# eggShield.net
KiCad netlist of a schematic drawn in EAGLE
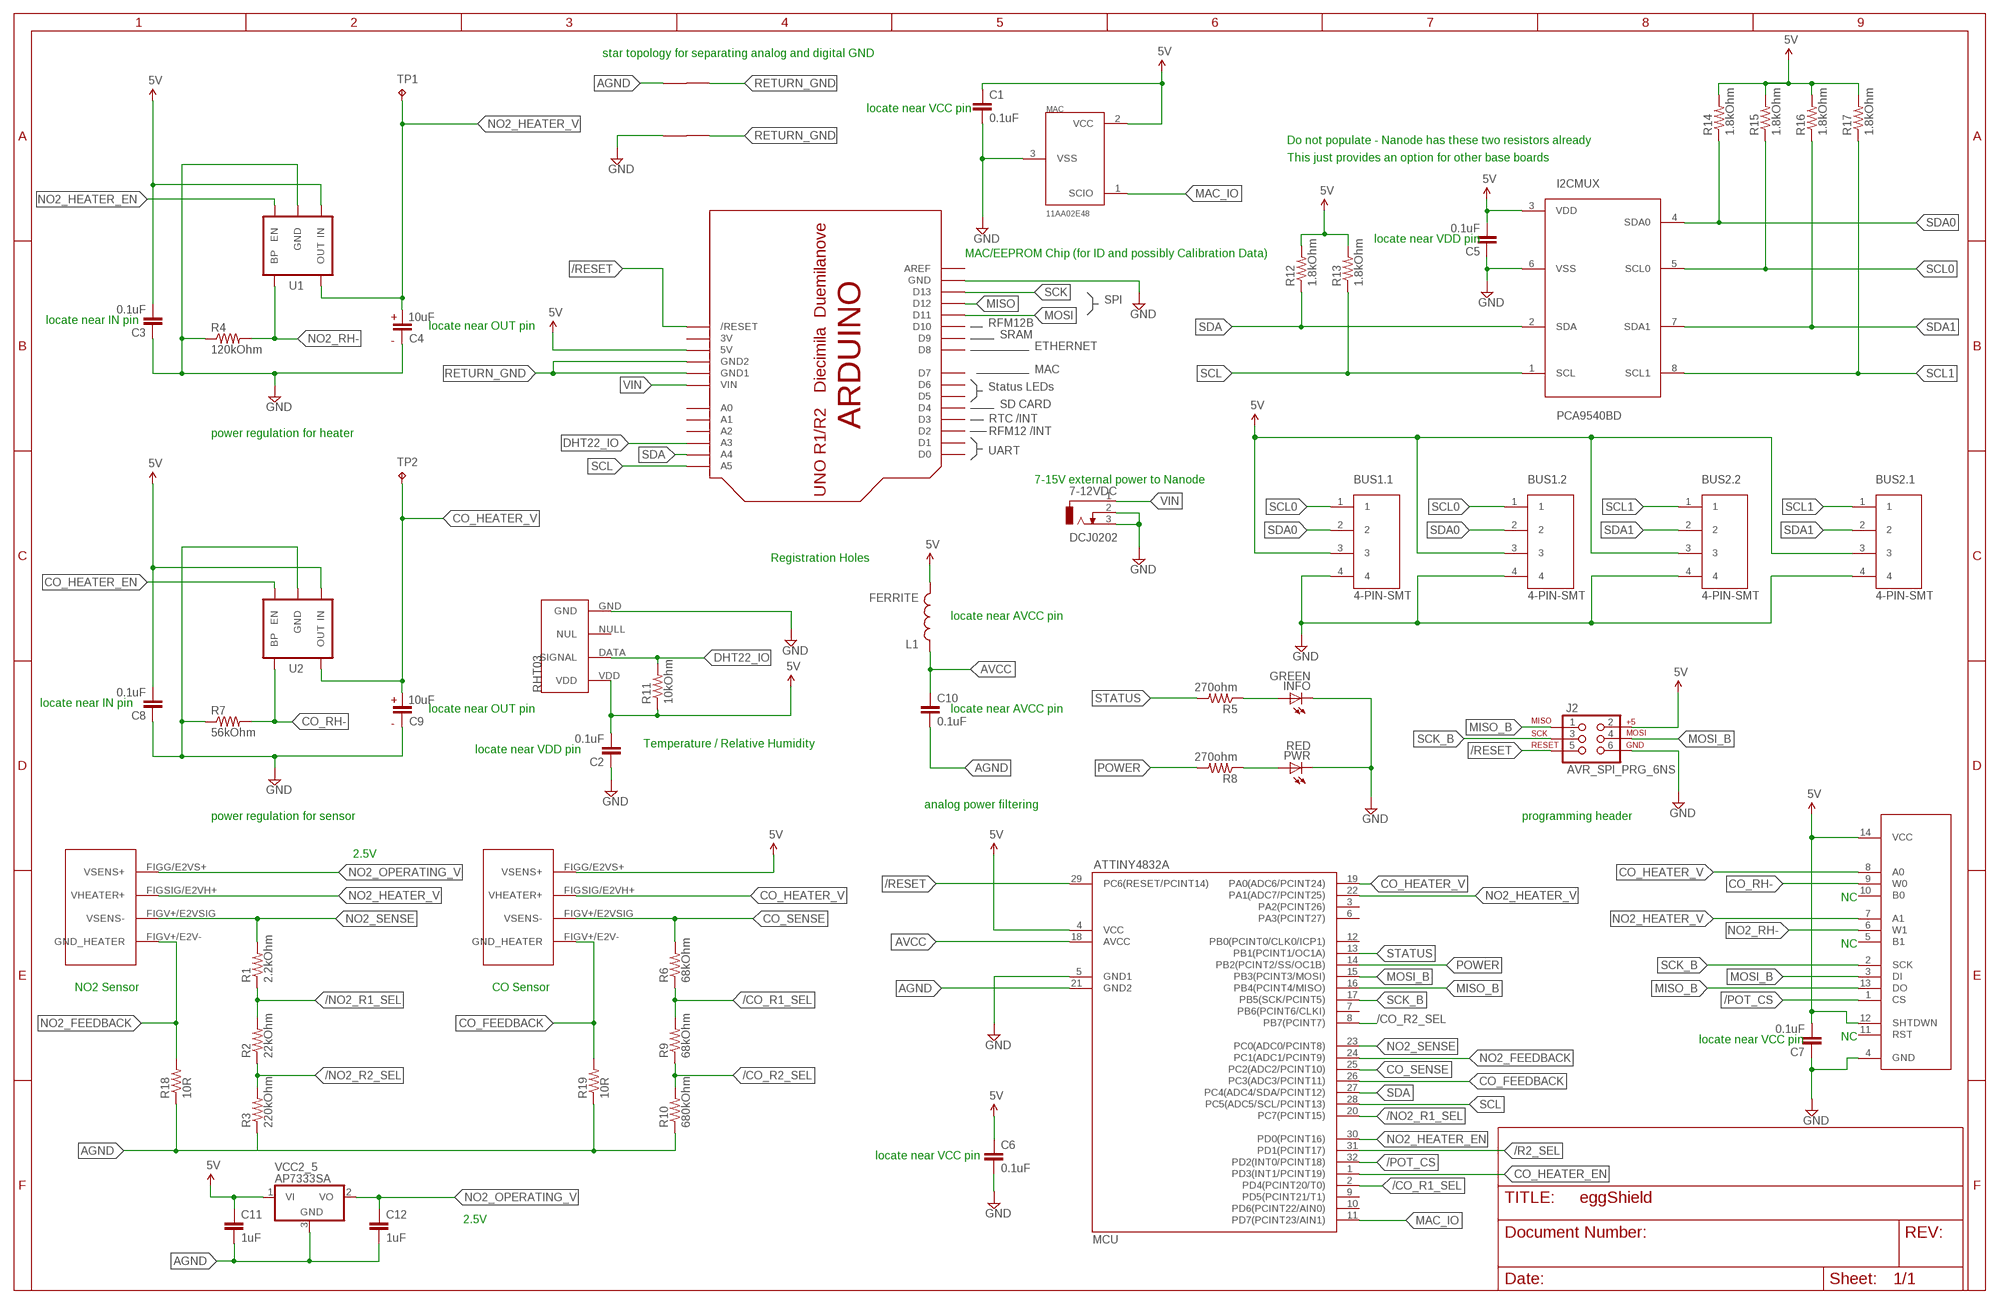
[diagram p0: schematic, sheet 1]

(export (version "E")
  (design (tool "Eeschema 10.0.6"))
  (components
    (comp (ref "7-12VDC")
      (value "DCJ0202")
      (footprint "eagle-import:DCJ0202")
      (libsource (lib "eagle-import") (part "DCJ0202"))
    )
    (comp (ref "BUS1.1")
      (value "4-PIN-SMT")
      (footprint "eagle-import:1775470-4")
      (libsource (lib "eagle-import") (part "4-PIN-SMT"))
    )
    (comp (ref "BUS1.2")
      (value "4-PIN-SMT")
      (footprint "eagle-import:1775470-4")
      (libsource (lib "eagle-import") (part "4-PIN-SMT"))
    )
    (comp (ref "BUS2.1")
      (value "4-PIN-SMT")
      (footprint "eagle-import:1775470-4")
      (libsource (lib "eagle-import") (part "4-PIN-SMT"))
    )
    (comp (ref "BUS2.2")
      (value "4-PIN-SMT")
      (footprint "eagle-import:1775470-4")
      (libsource (lib "eagle-import") (part "4-PIN-SMT"))
    )
    (comp (ref "C1")
      (value "0.1uF")
      (footprint "eagle-import:0805")
      (libsource (lib "eagle-import") (part "SparkFun-Passives_CAP0805"))
    )
    (comp (ref "C2")
      (value "0.1uF")
      (footprint "eagle-import:0805")
      (libsource (lib "eagle-import") (part "SparkFun-Passives_CAP0805"))
    )
    (comp (ref "C3")
      (value "0.1uF")
      (footprint "eagle-import:0805")
      (libsource (lib "eagle-import") (part "SparkFun-Passives_CAP0805"))
    )
    (comp (ref "C4")
      (value "10uF")
      (footprint "eagle-import:TYPE-B_ALUMINUM_CAN")
      (libsource (lib "eagle-import") (part "EEE-1EA100WR"))
    )
    (comp (ref "C5")
      (value "0.1uF")
      (footprint "eagle-import:0805")
      (libsource (lib "eagle-import") (part "SparkFun-Passives_CAP0805"))
    )
    (comp (ref "C6")
      (value "0.1uF")
      (footprint "eagle-import:0805")
      (libsource (lib "eagle-import") (part "SparkFun-Passives_CAP0805"))
    )
    (comp (ref "C7")
      (value "0.1uF")
      (footprint "eagle-import:0805")
      (libsource (lib "eagle-import") (part "SparkFun-Passives_CAP0805"))
    )
    (comp (ref "C8")
      (value "0.1uF")
      (footprint "eagle-import:0805")
      (libsource (lib "eagle-import") (part "SparkFun-Passives_CAP0805"))
    )
    (comp (ref "C9")
      (value "10uF")
      (footprint "eagle-import:TYPE-B_ALUMINUM_CAN")
      (libsource (lib "eagle-import") (part "EEE-1EA100WR"))
    )
    (comp (ref "C10")
      (value "0.1uF")
      (footprint "eagle-import:0805")
      (libsource (lib "eagle-import") (part "SparkFun-Passives_CAP0805"))
    )
    (comp (ref "C11")
      (value "1uF")
      (footprint "eagle-import:0805")
      (libsource (lib "eagle-import") (part "SparkFun-Passives_CAP0805"))
    )
    (comp (ref "C12")
      (value "1uF")
      (footprint "eagle-import:0805")
      (libsource (lib "eagle-import") (part "SparkFun-Passives_CAP0805"))
    )
    (comp (ref "CO")
      (value "E2V")
      (footprint "eagle-import:SR-4")
      (libsource (lib "eagle-import") (part "E2V"))
    )
    (comp (ref "DHT22")
      (value "RHT03")
      (footprint "eagle-import:1X04_LOCK")
      (libsource (lib "eagle-import") (part "RHT03"))
    )
    (comp (ref "I2CMUX")
      (value "PCA9540BD")
      (footprint "eagle-import:SO8")
      (libsource (lib "eagle-import") (part "PCA9540BD"))
    )
    (comp (ref "INFO")
      (value "GREEN")
      (footprint "eagle-import:CHIPLED_0805")
      (libsource (lib "eagle-import") (part "LEDCHIPLED_0805"))
    )
    (comp (ref "J2")
      (value "AVR_SPI_PRG_6NS")
      (footprint "eagle-import:2X3-NS")
      (libsource (lib "eagle-import") (part "AVR_SPI_PRG_6NS"))
    )
    (comp (ref "L1")
      (value "FERRITE")
      (footprint "eagle-import:0805")
      (libsource (lib "eagle-import") (part "INDUCTOR0805"))
    )
    (comp (ref "MAC")
      (value "11AA02E48")
      (footprint "eagle-import:SOT23")
      (libsource (lib "eagle-import") (part "11AA02E48"))
    )
    (comp (ref "MCU")
      (value "ATTINY4832A")
      (footprint "eagle-import:TQFP32-08")
      (libsource (lib "eagle-import") (part "ATTINY4832A"))
    )
    (comp (ref "N02")
      (value "E2V")
      (footprint "eagle-import:SR-4")
      (libsource (lib "eagle-import") (part "E2V"))
    )
    (comp (ref "PWR")
      (value "RED")
      (footprint "eagle-import:CHIPLED_0805")
      (libsource (lib "eagle-import") (part "LEDCHIPLED_0805"))
    )
    (comp (ref "R1")
      (value "2.2kOhm")
      (footprint "eagle-import:0805")
      (libsource (lib "eagle-import") (part "RESISTOR0805-RES"))
    )
    (comp (ref "R2")
      (value "22kOhm")
      (footprint "eagle-import:0805")
      (libsource (lib "eagle-import") (part "RESISTOR0805-RES"))
    )
    (comp (ref "R3")
      (value "220kOhm")
      (footprint "eagle-import:0805")
      (libsource (lib "eagle-import") (part "RESISTOR0805-RES"))
    )
    (comp (ref "R4")
      (value "120kOhm")
      (footprint "eagle-import:0805")
      (libsource (lib "eagle-import") (part "RESISTOR0805-RES"))
    )
    (comp (ref "R5")
      (value "270ohm")
      (footprint "eagle-import:0805")
      (libsource (lib "eagle-import") (part "RESISTOR0805-RES"))
    )
    (comp (ref "R6")
      (value "68kOhm")
      (footprint "eagle-import:0805")
      (libsource (lib "eagle-import") (part "RESISTOR0805-RES"))
    )
    (comp (ref "R7")
      (value "56kOhm")
      (footprint "eagle-import:0805")
      (libsource (lib "eagle-import") (part "RESISTOR0805-RES"))
    )
    (comp (ref "R8")
      (value "270ohm")
      (footprint "eagle-import:0805")
      (libsource (lib "eagle-import") (part "RESISTOR0805-RES"))
    )
    (comp (ref "R9")
      (value "68kOhm")
      (footprint "eagle-import:0805")
      (libsource (lib "eagle-import") (part "RESISTOR0805-RES"))
    )
    (comp (ref "R10")
      (value "680kOhm")
      (footprint "eagle-import:0805")
      (libsource (lib "eagle-import") (part "RESISTOR0805-RES"))
    )
    (comp (ref "R11")
      (value "10kOhm")
      (footprint "eagle-import:0805")
      (libsource (lib "eagle-import") (part "RESISTOR0805-RES"))
    )
    (comp (ref "R12")
      (value "1.8kOhm")
      (footprint "eagle-import:0805")
      (libsource (lib "eagle-import") (part "RESISTOR0805-RES"))
    )
    (comp (ref "R13")
      (value "1.8kOhm")
      (footprint "eagle-import:0805")
      (libsource (lib "eagle-import") (part "RESISTOR0805-RES"))
    )
    (comp (ref "R14")
      (value "1.8kOhm")
      (footprint "eagle-import:0805")
      (libsource (lib "eagle-import") (part "RESISTOR0805-RES"))
    )
    (comp (ref "R15")
      (value "1.8kOhm")
      (footprint "eagle-import:0805")
      (libsource (lib "eagle-import") (part "RESISTOR0805-RES"))
    )
    (comp (ref "R16")
      (value "1.8kOhm")
      (footprint "eagle-import:0805")
      (libsource (lib "eagle-import") (part "RESISTOR0805-RES"))
    )
    (comp (ref "R17")
      (value "1.8kOhm")
      (footprint "eagle-import:0805")
      (libsource (lib "eagle-import") (part "RESISTOR0805-RES"))
    )
    (comp (ref "R18")
      (value "10R")
      (footprint "eagle-import:0805")
      (libsource (lib "eagle-import") (part "RESISTOR0805-RES"))
    )
    (comp (ref "R19")
      (value "10R")
      (footprint "eagle-import:0805")
      (libsource (lib "eagle-import") (part "RESISTOR0805-RES"))
    )
    (comp (ref "TP1")
      (value "TPPAD1-13")
      (footprint "eagle-import:P1-13")
      (libsource (lib "eagle-import") (part "TPPAD1-13"))
    )
    (comp (ref "TP2")
      (value "TPPAD1-13")
      (footprint "eagle-import:P1-13")
      (libsource (lib "eagle-import") (part "TPPAD1-13"))
    )
    (comp (ref "U$7")
      (value "ARDUINO-NOHOLE")
      (footprint "eagle-import:ARDUINO-NOHOLE")
      (libsource (lib "eagle-import") (part "ARDUINO-NOHOLE"))
    )
    (comp (ref "U$13")
      (value "PLANE_COUPLER")
      (footprint "eagle-import:PLANE_COUPLER")
      (libsource (lib "eagle-import") (part "PLANE_COUPLER"))
    )
    (comp (ref "U$14")
      (value "PLANE_COUPLER")
      (footprint "eagle-import:PLANE_COUPLER")
      (libsource (lib "eagle-import") (part "PLANE_COUPLER"))
    )
    (comp (ref "U1")
      (value "V_REG_LDOSMD")
      (footprint "eagle-import:SOT23-5")
      (libsource (lib "eagle-import") (part "V_REG_LDOSMD"))
    )
    (comp (ref "U2")
      (value "V_REG_LDOSMD")
      (footprint "eagle-import:SOT23-5")
      (libsource (lib "eagle-import") (part "V_REG_LDOSMD"))
    )
    (comp (ref "U3")
      (value "MCP42XXX")
      (footprint "eagle-import:SO014")
      (libsource (lib "eagle-import") (part "MCP42XXX"))
    )
    (comp (ref "VCC2_5")
      (value "AP7333SA")
      (footprint "eagle-import:SOT-23-3")
      (libsource (lib "eagle-import") (part "AP7333SA"))
    )
  )
  (nets
    (net (code "1") (name "/3V") (class "Default")
      (node (ref "U$7") (pin "3V") (pinfunction "3V_3V") (pintype "power_in"))
    )
    (net (code "2") (name "5V") (class "Default")
      (node (ref "BUS1.1") (pin "3") (pinfunction "3_3") (pintype "bidirectional"))
      (node (ref "BUS1.2") (pin "3") (pinfunction "3_3") (pintype "bidirectional"))
      (node (ref "BUS2.1") (pin "3") (pinfunction "3_3") (pintype "bidirectional"))
      (node (ref "BUS2.2") (pin "3") (pinfunction "3_3") (pintype "bidirectional"))
      (node (ref "C1") (pin "1") (pinfunction "1_1") (pintype "passive"))
      (node (ref "C11") (pin "1") (pinfunction "1_1") (pintype "passive"))
      (node (ref "C2") (pin "2") (pinfunction "2_2") (pintype "passive"))
      (node (ref "C3") (pin "2") (pinfunction "2_2") (pintype "passive"))
      (node (ref "C5") (pin "2") (pinfunction "2_2") (pintype "passive"))
      (node (ref "C6") (pin "1") (pinfunction "1_1") (pintype "passive"))
      (node (ref "C7") (pin "2") (pinfunction "2_2") (pintype "passive"))
      (node (ref "C8") (pin "2") (pinfunction "2_2") (pintype "passive"))
      (node (ref "CO") (pin "FIGG/E2VS+") (pinfunction "VSENS+_FIGG/E2VS+") (pintype "bidirectional"))
      (node (ref "DHT22") (pin "VDD") (pinfunction "VDD_VDD") (pintype "bidirectional"))
      (node (ref "I2CMUX") (pin "3") (pinfunction "VDD_3") (pintype "power_in"))
      (node (ref "J2") (pin "2") (pinfunction "2_2") (pintype "passive"))
      (node (ref "L1") (pin "2") (pinfunction "2_2") (pintype "passive"))
      (node (ref "MAC") (pin "2") (pinfunction "VCC_2") (pintype "bidirectional"))
      (node (ref "MCU") (pin "4") (pinfunction "VCC_4") (pintype "power_in"))
      (node (ref "R11") (pin "1") (pinfunction "1_1") (pintype "passive"))
      (node (ref "R12") (pin "2") (pinfunction "2_2") (pintype "passive"))
      (node (ref "R13") (pin "2") (pinfunction "2_2") (pintype "passive"))
      (node (ref "R14") (pin "2") (pinfunction "2_2") (pintype "passive"))
      (node (ref "R15") (pin "2") (pinfunction "2_2") (pintype "passive"))
      (node (ref "R16") (pin "2") (pinfunction "2_2") (pintype "passive"))
      (node (ref "R17") (pin "2") (pinfunction "2_2") (pintype "passive"))
      (node (ref "U$7") (pin "5V") (pinfunction "5V_5V") (pintype "power_in"))
      (node (ref "U1") (pin "1") (pinfunction "IN_1") (pintype "input"))
      (node (ref "U2") (pin "1") (pinfunction "IN_1") (pintype "input"))
      (node (ref "U3") (pin "12") (pinfunction "SHTDWN_12") (pintype "bidirectional"))
      (node (ref "U3") (pin "14") (pinfunction "VCC_14") (pintype "bidirectional"))
      (node (ref "VCC2_5") (pin "1") (pinfunction "VI_1") (pintype "input"))
    )
    (net (code "3") (name "AGND") (class "Default")
      (node (ref "C10") (pin "2") (pinfunction "2_2") (pintype "passive"))
      (node (ref "C11") (pin "2") (pinfunction "2_2") (pintype "passive"))
      (node (ref "C12") (pin "2") (pinfunction "2_2") (pintype "passive"))
      (node (ref "MCU") (pin "21") (pinfunction "GND2_21") (pintype "power_in"))
      (node (ref "R10") (pin "1") (pinfunction "1_1") (pintype "passive"))
      (node (ref "R18") (pin "1") (pinfunction "1_1") (pintype "passive"))
      (node (ref "R19") (pin "1") (pinfunction "1_1") (pintype "passive"))
      (node (ref "R3") (pin "1") (pinfunction "1_1") (pintype "passive"))
      (node (ref "U$13") (pin "1") (pinfunction "P$1_1") (pintype "bidirectional"))
      (node (ref "VCC2_5") (pin "3") (pinfunction "GND_3") (pintype "input"))
    )
    (net (code "4") (name "AVCC") (class "Default")
      (node (ref "C10") (pin "1") (pinfunction "1_1") (pintype "passive"))
      (node (ref "L1") (pin "1") (pinfunction "1_1") (pintype "passive"))
      (node (ref "MCU") (pin "18") (pinfunction "AVCC_18") (pintype "power_in"))
    )
    (net (code "5") (name "CO_FEEDBACK") (class "Default")
      (node (ref "CO") (pin "FIGV+/E2V-") (pinfunction "GND_HEATER_FIGV+/E2V-") (pintype "bidirectional"))
      (node (ref "MCU") (pin "26") (pinfunction "PC3(ADC3/PCINT11)_26") (pintype "bidirectional"))
      (node (ref "R19") (pin "2") (pinfunction "2_2") (pintype "passive"))
    )
    (net (code "6") (name "CO_HEATER_EN") (class "Default")
      (node (ref "MCU") (pin "1") (pinfunction "PD3(INT1/PCINT19)_1") (pintype "bidirectional"))
      (node (ref "U2") (pin "3") (pinfunction "EN_3") (pintype "input"))
    )
    (net (code "7") (name "CO_HEATER_V") (class "Default")
      (node (ref "C9") (pin "P$1") (pinfunction "1_P$1") (pintype "passive"))
      (node (ref "CO") (pin "FIGSIG/E2VH+") (pinfunction "VHEATER+_FIGSIG/E2VH+") (pintype "bidirectional"))
      (node (ref "MCU") (pin "19") (pinfunction "PA0(ADC6/PCINT24)_19") (pintype "bidirectional"))
      (node (ref "TP2") (pin "TP") (pinfunction "TP_TP") (pintype "input"))
      (node (ref "U2") (pin "5") (pinfunction "OUT_5") (pintype "passive"))
      (node (ref "U3") (pin "8") (pinfunction "A0_8") (pintype "bidirectional"))
    )
    (net (code "8") (name "CO_RH-") (class "Default")
      (node (ref "R7") (pin "2") (pinfunction "2_2") (pintype "passive"))
      (node (ref "U2") (pin "4") (pinfunction "BP_4") (pintype "input"))
      (node (ref "U3") (pin "9") (pinfunction "W0_9") (pintype "bidirectional"))
    )
    (net (code "9") (name "CO_SENSE") (class "Default")
      (node (ref "CO") (pin "FIGV+/E2VSIG") (pinfunction "VSENS-_FIGV+/E2VSIG") (pintype "bidirectional"))
      (node (ref "MCU") (pin "25") (pinfunction "PC2(ADC2/PCINT10)_25") (pintype "bidirectional"))
      (node (ref "R6") (pin "2") (pinfunction "2_2") (pintype "passive"))
    )
    (net (code "10") (name "DHT22_IO") (class "Default")
      (node (ref "DHT22") (pin "DATA") (pinfunction "SIGNAL_DATA") (pintype "bidirectional"))
      (node (ref "R11") (pin "2") (pinfunction "2_2") (pintype "passive"))
      (node (ref "U$7") (pin "A3") (pinfunction "A3_A3") (pintype "bidirectional"))
    )
    (net (code "11") (name "GND") (class "Default")
      (node (ref "7-12VDC") (pin "2") (pinfunction "2_2") (pintype "passive"))
      (node (ref "7-12VDC") (pin "3") (pinfunction "3_3") (pintype "passive"))
      (node (ref "BUS1.1") (pin "4") (pinfunction "4_4") (pintype "bidirectional"))
      (node (ref "BUS1.2") (pin "4") (pinfunction "4_4") (pintype "bidirectional"))
      (node (ref "BUS2.1") (pin "4") (pinfunction "4_4") (pintype "bidirectional"))
      (node (ref "BUS2.2") (pin "4") (pinfunction "4_4") (pintype "bidirectional"))
      (node (ref "C1") (pin "2") (pinfunction "2_2") (pintype "passive"))
      (node (ref "C2") (pin "1") (pinfunction "1_1") (pintype "passive"))
      (node (ref "C3") (pin "1") (pinfunction "1_1") (pintype "passive"))
      (node (ref "C4") (pin "P$2") (pinfunction "2_P$2") (pintype "passive"))
      (node (ref "C5") (pin "1") (pinfunction "1_1") (pintype "passive"))
      (node (ref "C6") (pin "2") (pinfunction "2_2") (pintype "passive"))
      (node (ref "C7") (pin "1") (pinfunction "1_1") (pintype "passive"))
      (node (ref "C8") (pin "1") (pinfunction "1_1") (pintype "passive"))
      (node (ref "C9") (pin "P$2") (pinfunction "2_P$2") (pintype "passive"))
      (node (ref "DHT22") (pin "GND") (pinfunction "GND_GND") (pintype "bidirectional"))
      (node (ref "I2CMUX") (pin "6") (pinfunction "VSS_6") (pintype "power_in"))
      (node (ref "INFO") (pin "C") (pinfunction "C_C") (pintype "passive"))
      (node (ref "J2") (pin "6") (pinfunction "6_6") (pintype "passive"))
      (node (ref "MAC") (pin "3") (pinfunction "VSS_3") (pintype "bidirectional"))
      (node (ref "MCU") (pin "5") (pinfunction "GND1_5") (pintype "power_in"))
      (node (ref "PWR") (pin "C") (pinfunction "C_C") (pintype "passive"))
      (node (ref "R4") (pin "1") (pinfunction "1_1") (pintype "passive"))
      (node (ref "R7") (pin "1") (pinfunction "1_1") (pintype "passive"))
      (node (ref "U$14") (pin "1") (pinfunction "P$1_1") (pintype "bidirectional"))
      (node (ref "U$7") (pin "GND") (pinfunction "GND_GND") (pintype "power_in"))
      (node (ref "U1") (pin "2") (pinfunction "GND_2") (pintype "input"))
      (node (ref "U2") (pin "2") (pinfunction "GND_2") (pintype "input"))
      (node (ref "U3") (pin "4") (pinfunction "GND_4") (pintype "bidirectional"))
    )
    (net (code "12") (name "MAC_IO") (class "Default")
      (node (ref "MAC") (pin "1") (pinfunction "SCIO_1") (pintype "bidirectional"))
      (node (ref "MCU") (pin "11") (pinfunction "PD7(PCINT23/AIN1)_11") (pintype "bidirectional"))
    )
    (net (code "13") (name "MISO") (class "Default")
      (node (ref "U$7") (pin "D12") (pinfunction "D12_D12") (pintype "bidirectional"))
    )
    (net (code "14") (name "MISO_B") (class "Default")
      (node (ref "J2") (pin "1") (pinfunction "1_1") (pintype "passive"))
      (node (ref "MCU") (pin "16") (pinfunction "PB4(PCINT4/MISO)_16") (pintype "bidirectional"))
      (node (ref "U3") (pin "13") (pinfunction "DO_13") (pintype "bidirectional"))
    )
    (net (code "15") (name "MOSI") (class "Default")
      (node (ref "U$7") (pin "D11") (pinfunction "D11_D11") (pintype "bidirectional"))
    )
    (net (code "16") (name "MOSI_B") (class "Default")
      (node (ref "J2") (pin "4") (pinfunction "4_4") (pintype "passive"))
      (node (ref "MCU") (pin "15") (pinfunction "PB3(PCINT3/MOSI)_15") (pintype "bidirectional"))
      (node (ref "U3") (pin "3") (pinfunction "DI_3") (pintype "bidirectional"))
    )
    (net (code "17") (name "NO2_FEEDBACK") (class "Default")
      (node (ref "MCU") (pin "24") (pinfunction "PC1(ADC1/PCINT9)_24") (pintype "bidirectional"))
      (node (ref "N02") (pin "FIGV+/E2V-") (pinfunction "GND_HEATER_FIGV+/E2V-") (pintype "bidirectional"))
      (node (ref "R18") (pin "2") (pinfunction "2_2") (pintype "passive"))
    )
    (net (code "18") (name "NO2_HEATER_EN") (class "Default")
      (node (ref "MCU") (pin "30") (pinfunction "PD0(PCINT16)_30") (pintype "bidirectional"))
      (node (ref "U1") (pin "3") (pinfunction "EN_3") (pintype "input"))
    )
    (net (code "19") (name "NO2_HEATER_V") (class "Default")
      (node (ref "C4") (pin "P$1") (pinfunction "1_P$1") (pintype "passive"))
      (node (ref "MCU") (pin "22") (pinfunction "PA1(ADC7/PCINT25)_22") (pintype "bidirectional"))
      (node (ref "N02") (pin "FIGSIG/E2VH+") (pinfunction "VHEATER+_FIGSIG/E2VH+") (pintype "bidirectional"))
      (node (ref "TP1") (pin "TP") (pinfunction "TP_TP") (pintype "input"))
      (node (ref "U1") (pin "5") (pinfunction "OUT_5") (pintype "passive"))
      (node (ref "U3") (pin "7") (pinfunction "A1_7") (pintype "bidirectional"))
    )
    (net (code "20") (name "NO2_OPERATING_V") (class "Default")
      (node (ref "C12") (pin "1") (pinfunction "1_1") (pintype "passive"))
      (node (ref "N02") (pin "FIGG/E2VS+") (pinfunction "VSENS+_FIGG/E2VS+") (pintype "bidirectional"))
      (node (ref "VCC2_5") (pin "2") (pinfunction "VO_2") (pintype "passive"))
    )
    (net (code "21") (name "NO2_RH-") (class "Default")
      (node (ref "R4") (pin "2") (pinfunction "2_2") (pintype "passive"))
      (node (ref "U1") (pin "4") (pinfunction "BP_4") (pintype "input"))
      (node (ref "U3") (pin "6") (pinfunction "W1_6") (pintype "bidirectional"))
    )
    (net (code "22") (name "NO2_SENSE") (class "Default")
      (node (ref "MCU") (pin "23") (pinfunction "PC0(ADC0/PCINT8)_23") (pintype "bidirectional"))
      (node (ref "N02") (pin "FIGV+/E2VSIG") (pinfunction "VSENS-_FIGV+/E2VSIG") (pintype "bidirectional"))
      (node (ref "R1") (pin "2") (pinfunction "2_2") (pintype "passive"))
    )
    (net (code "23") (name "Net-(INFO-PadA)") (class "Default")
      (node (ref "INFO") (pin "A") (pinfunction "A_A") (pintype "passive"))
      (node (ref "R5") (pin "1") (pinfunction "1_1") (pintype "passive"))
    )
    (net (code "24") (name "Net-(PWR-PadA)") (class "Default")
      (node (ref "PWR") (pin "A") (pinfunction "A_A") (pintype "passive"))
      (node (ref "R8") (pin "1") (pinfunction "1_1") (pintype "passive"))
    )
    (net (code "25") (name "POWER") (class "Default")
      (node (ref "MCU") (pin "14") (pinfunction "PB2(PCINT2/SS/OC1B)_14") (pintype "bidirectional"))
      (node (ref "R8") (pin "2") (pinfunction "2_2") (pintype "passive"))
    )
    (net (code "26") (name "RETURN_GND") (class "Default")
      (node (ref "U$13") (pin "2") (pinfunction "P$2_2") (pintype "bidirectional"))
      (node (ref "U$14") (pin "2") (pinfunction "P$2_2") (pintype "bidirectional"))
      (node (ref "U$7") (pin "GND1") (pinfunction "GND1_GND1") (pintype "power_in"))
      (node (ref "U$7") (pin "GND2") (pinfunction "GND2_GND2") (pintype "power_in"))
    )
    (net (code "27") (name "SCK") (class "Default")
      (node (ref "U$7") (pin "D13") (pinfunction "D13_D13") (pintype "bidirectional"))
    )
    (net (code "28") (name "SCK_B") (class "Default")
      (node (ref "J2") (pin "3") (pinfunction "3_3") (pintype "passive"))
      (node (ref "MCU") (pin "17") (pinfunction "PB5(SCK/PCINT5)_17") (pintype "bidirectional"))
      (node (ref "U3") (pin "2") (pinfunction "SCK_2") (pintype "bidirectional"))
    )
    (net (code "29") (name "SCL") (class "Default")
      (node (ref "I2CMUX") (pin "1") (pinfunction "SCL_1") (pintype "bidirectional"))
      (node (ref "MCU") (pin "28") (pinfunction "PC5(ADC5/SCL/PCINT13)_28") (pintype "bidirectional"))
      (node (ref "R13") (pin "1") (pinfunction "1_1") (pintype "passive"))
      (node (ref "U$7") (pin "A5") (pinfunction "A5_A5") (pintype "bidirectional"))
    )
    (net (code "30") (name "SCL0") (class "Default")
      (node (ref "BUS1.1") (pin "1") (pinfunction "1_1") (pintype "bidirectional"))
      (node (ref "BUS1.2") (pin "1") (pinfunction "1_1") (pintype "bidirectional"))
      (node (ref "I2CMUX") (pin "5") (pinfunction "SCL0_5") (pintype "bidirectional"))
      (node (ref "R15") (pin "1") (pinfunction "1_1") (pintype "passive"))
    )
    (net (code "31") (name "SCL1") (class "Default")
      (node (ref "BUS2.1") (pin "1") (pinfunction "1_1") (pintype "bidirectional"))
      (node (ref "BUS2.2") (pin "1") (pinfunction "1_1") (pintype "bidirectional"))
      (node (ref "I2CMUX") (pin "8") (pinfunction "SCL1_8") (pintype "bidirectional"))
      (node (ref "R17") (pin "1") (pinfunction "1_1") (pintype "passive"))
    )
    (net (code "32") (name "SDA") (class "Default")
      (node (ref "I2CMUX") (pin "2") (pinfunction "SDA_2") (pintype "bidirectional"))
      (node (ref "MCU") (pin "27") (pinfunction "PC4(ADC4/SDA/PCINT12)_27") (pintype "bidirectional"))
      (node (ref "R12") (pin "1") (pinfunction "1_1") (pintype "passive"))
      (node (ref "U$7") (pin "A4") (pinfunction "A4_A4") (pintype "bidirectional"))
    )
    (net (code "33") (name "SDA0") (class "Default")
      (node (ref "BUS1.1") (pin "2") (pinfunction "2_2") (pintype "bidirectional"))
      (node (ref "BUS1.2") (pin "2") (pinfunction "2_2") (pintype "bidirectional"))
      (node (ref "I2CMUX") (pin "4") (pinfunction "SDA0_4") (pintype "bidirectional"))
      (node (ref "R14") (pin "1") (pinfunction "1_1") (pintype "passive"))
    )
    (net (code "34") (name "SDA1") (class "Default")
      (node (ref "BUS2.1") (pin "2") (pinfunction "2_2") (pintype "bidirectional"))
      (node (ref "BUS2.2") (pin "2") (pinfunction "2_2") (pintype "bidirectional"))
      (node (ref "I2CMUX") (pin "7") (pinfunction "SDA1_7") (pintype "bidirectional"))
      (node (ref "R16") (pin "1") (pinfunction "1_1") (pintype "passive"))
    )
    (net (code "35") (name "STATUS") (class "Default")
      (node (ref "MCU") (pin "13") (pinfunction "PB1(PCINT1/OC1A)_13") (pintype "bidirectional"))
      (node (ref "R5") (pin "2") (pinfunction "2_2") (pintype "passive"))
    )
    (net (code "36") (name "VIN") (class "Default")
      (node (ref "7-12VDC") (pin "1") (pinfunction "1_1") (pintype "passive"))
      (node (ref "U$7") (pin "VIN") (pinfunction "VIN_VIN") (pintype "power_in"))
    )
    (net (code "37") (name "unconnected-(DHT22-NUL-PadNULL)") (class "Default")
      (node (ref "DHT22") (pin "NULL") (pinfunction "NUL_NULL") (pintype "bidirectional"))
    )
    (net (code "38") (name "unconnected-(MCU-PA2(PCINT26)-Pad3)") (class "Default")
      (node (ref "MCU") (pin "3") (pinfunction "PA2(PCINT26)_3") (pintype "bidirectional"))
    )
    (net (code "39") (name "unconnected-(MCU-PA3(PCINT27)-Pad6)") (class "Default")
      (node (ref "MCU") (pin "6") (pinfunction "PA3(PCINT27)_6") (pintype "bidirectional"))
    )
    (net (code "40") (name "unconnected-(MCU-PB0(PCINT0{slash}CLK0{slash}ICP1)-Pad12)") (class "Default")
      (node (ref "MCU") (pin "12") (pinfunction "PB0(PCINT0/CLK0/ICP1)_12") (pintype "bidirectional"))
    )
    (net (code "41") (name "unconnected-(MCU-PB6(PCINT6{slash}CLKI)-Pad7)") (class "Default")
      (node (ref "MCU") (pin "7") (pinfunction "PB6(PCINT6/CLKI)_7") (pintype "bidirectional"))
    )
    (net (code "42") (name "unconnected-(MCU-PD5(PCINT21{slash}T1)-Pad9)") (class "Default")
      (node (ref "MCU") (pin "9") (pinfunction "PD5(PCINT21/T1)_9") (pintype "bidirectional"))
    )
    (net (code "43") (name "unconnected-(MCU-PD6(PCINT22{slash}AIN0)-Pad10)") (class "Default")
      (node (ref "MCU") (pin "10") (pinfunction "PD6(PCINT22/AIN0)_10") (pintype "bidirectional"))
    )
    (net (code "44") (name "unconnected-(U$7-PadA0)") (class "Default")
      (node (ref "U$7") (pin "A0") (pinfunction "A0_A0") (pintype "bidirectional"))
    )
    (net (code "45") (name "unconnected-(U$7-PadA1)") (class "Default")
      (node (ref "U$7") (pin "A1") (pinfunction "A1_A1") (pintype "bidirectional"))
    )
    (net (code "46") (name "unconnected-(U$7-PadA2)") (class "Default")
      (node (ref "U$7") (pin "A2") (pinfunction "A2_A2") (pintype "bidirectional"))
    )
    (net (code "47") (name "unconnected-(U$7-PadAREF)") (class "Default")
      (node (ref "U$7") (pin "AREF") (pinfunction "AREF_AREF") (pintype "bidirectional"))
    )
    (net (code "48") (name "unconnected-(U$7-PadD0)") (class "Default")
      (node (ref "U$7") (pin "D0") (pinfunction "D0_D0") (pintype "bidirectional"))
    )
    (net (code "49") (name "unconnected-(U$7-PadD1)") (class "Default")
      (node (ref "U$7") (pin "D1") (pinfunction "D1_D1") (pintype "bidirectional"))
    )
    (net (code "50") (name "unconnected-(U$7-PadD2)") (class "Default")
      (node (ref "U$7") (pin "D2") (pinfunction "D2_D2") (pintype "bidirectional"))
    )
    (net (code "51") (name "unconnected-(U$7-PadD3)") (class "Default")
      (node (ref "U$7") (pin "D3") (pinfunction "D3_D3") (pintype "bidirectional"))
    )
    (net (code "52") (name "unconnected-(U$7-PadD4)") (class "Default")
      (node (ref "U$7") (pin "D4") (pinfunction "D4_D4") (pintype "bidirectional"))
    )
    (net (code "53") (name "unconnected-(U$7-PadD5)") (class "Default")
      (node (ref "U$7") (pin "D5") (pinfunction "D5_D5") (pintype "bidirectional"))
    )
    (net (code "54") (name "unconnected-(U$7-PadD6)") (class "Default")
      (node (ref "U$7") (pin "D6") (pinfunction "D6_D6") (pintype "bidirectional"))
    )
    (net (code "55") (name "unconnected-(U$7-PadD7)") (class "Default")
      (node (ref "U$7") (pin "D7") (pinfunction "D7_D7") (pintype "bidirectional"))
    )
    (net (code "56") (name "unconnected-(U$7-PadD8)") (class "Default")
      (node (ref "U$7") (pin "D8") (pinfunction "D8_D8") (pintype "bidirectional"))
    )
    (net (code "57") (name "unconnected-(U$7-PadD9)") (class "Default")
      (node (ref "U$7") (pin "D9") (pinfunction "D9_D9") (pintype "bidirectional"))
    )
    (net (code "58") (name "unconnected-(U$7-PadD10)") (class "Default")
      (node (ref "U$7") (pin "D10") (pinfunction "D10_D10") (pintype "bidirectional"))
    )
    (net (code "59") (name "unconnected-(U3-B0-Pad10)") (class "Default")
      (node (ref "U3") (pin "10") (pinfunction "B0_10") (pintype "bidirectional"))
    )
    (net (code "60") (name "unconnected-(U3-B1-Pad5)") (class "Default")
      (node (ref "U3") (pin "5") (pinfunction "B1_5") (pintype "bidirectional"))
    )
    (net (code "61") (name "unconnected-(U3-RST-Pad11)") (class "Default")
      (node (ref "U3") (pin "11") (pinfunction "RST_11") (pintype "bidirectional"))
    )
    (net (code "62") (name "{slash}CO_R1_SEL") (class "Default")
      (node (ref "MCU") (pin "2") (pinfunction "PD4(PCINT20/T0)_2") (pintype "bidirectional"))
      (node (ref "R6") (pin "1") (pinfunction "1_1") (pintype "passive"))
      (node (ref "R9") (pin "2") (pinfunction "2_2") (pintype "passive"))
    )
    (net (code "63") (name "{slash}CO_R2_SEL") (class "Default")
      (node (ref "MCU") (pin "8") (pinfunction "PB7(PCINT7)_8") (pintype "bidirectional"))
      (node (ref "R10") (pin "2") (pinfunction "2_2") (pintype "passive"))
      (node (ref "R9") (pin "1") (pinfunction "1_1") (pintype "passive"))
    )
    (net (code "64") (name "{slash}NO2_R1_SEL") (class "Default")
      (node (ref "MCU") (pin "20") (pinfunction "PC7(PCINT15)_20") (pintype "bidirectional"))
      (node (ref "R1") (pin "1") (pinfunction "1_1") (pintype "passive"))
      (node (ref "R2") (pin "2") (pinfunction "2_2") (pintype "passive"))
    )
    (net (code "65") (name "{slash}NO2_R2_SEL") (class "Default")
      (node (ref "R2") (pin "1") (pinfunction "1_1") (pintype "passive"))
      (node (ref "R3") (pin "2") (pinfunction "2_2") (pintype "passive"))
    )
    (net (code "66") (name "{slash}POT_CS") (class "Default")
      (node (ref "MCU") (pin "32") (pinfunction "PD2(INT0/PCINT18)_32") (pintype "bidirectional"))
      (node (ref "U3") (pin "1") (pinfunction "CS_1") (pintype "bidirectional"))
    )
    (net (code "67") (name "{slash}R2_SEL") (class "Default")
      (node (ref "MCU") (pin "31") (pinfunction "PD1(PCINT17)_31") (pintype "bidirectional"))
    )
    (net (code "68") (name "{slash}RESET") (class "Default")
      (node (ref "J2") (pin "5") (pinfunction "5_5") (pintype "passive"))
      (node (ref "MCU") (pin "29") (pinfunction "PC6(RESET/PCINT14)_29") (pintype "bidirectional"))
      (node (ref "U$7") (pin "RESET") (pinfunction "/RESET_RESET") (pintype "bidirectional"))
    )
  )
)
